# riser.net
KiCad netlist of a schematic drawn in EAGLE
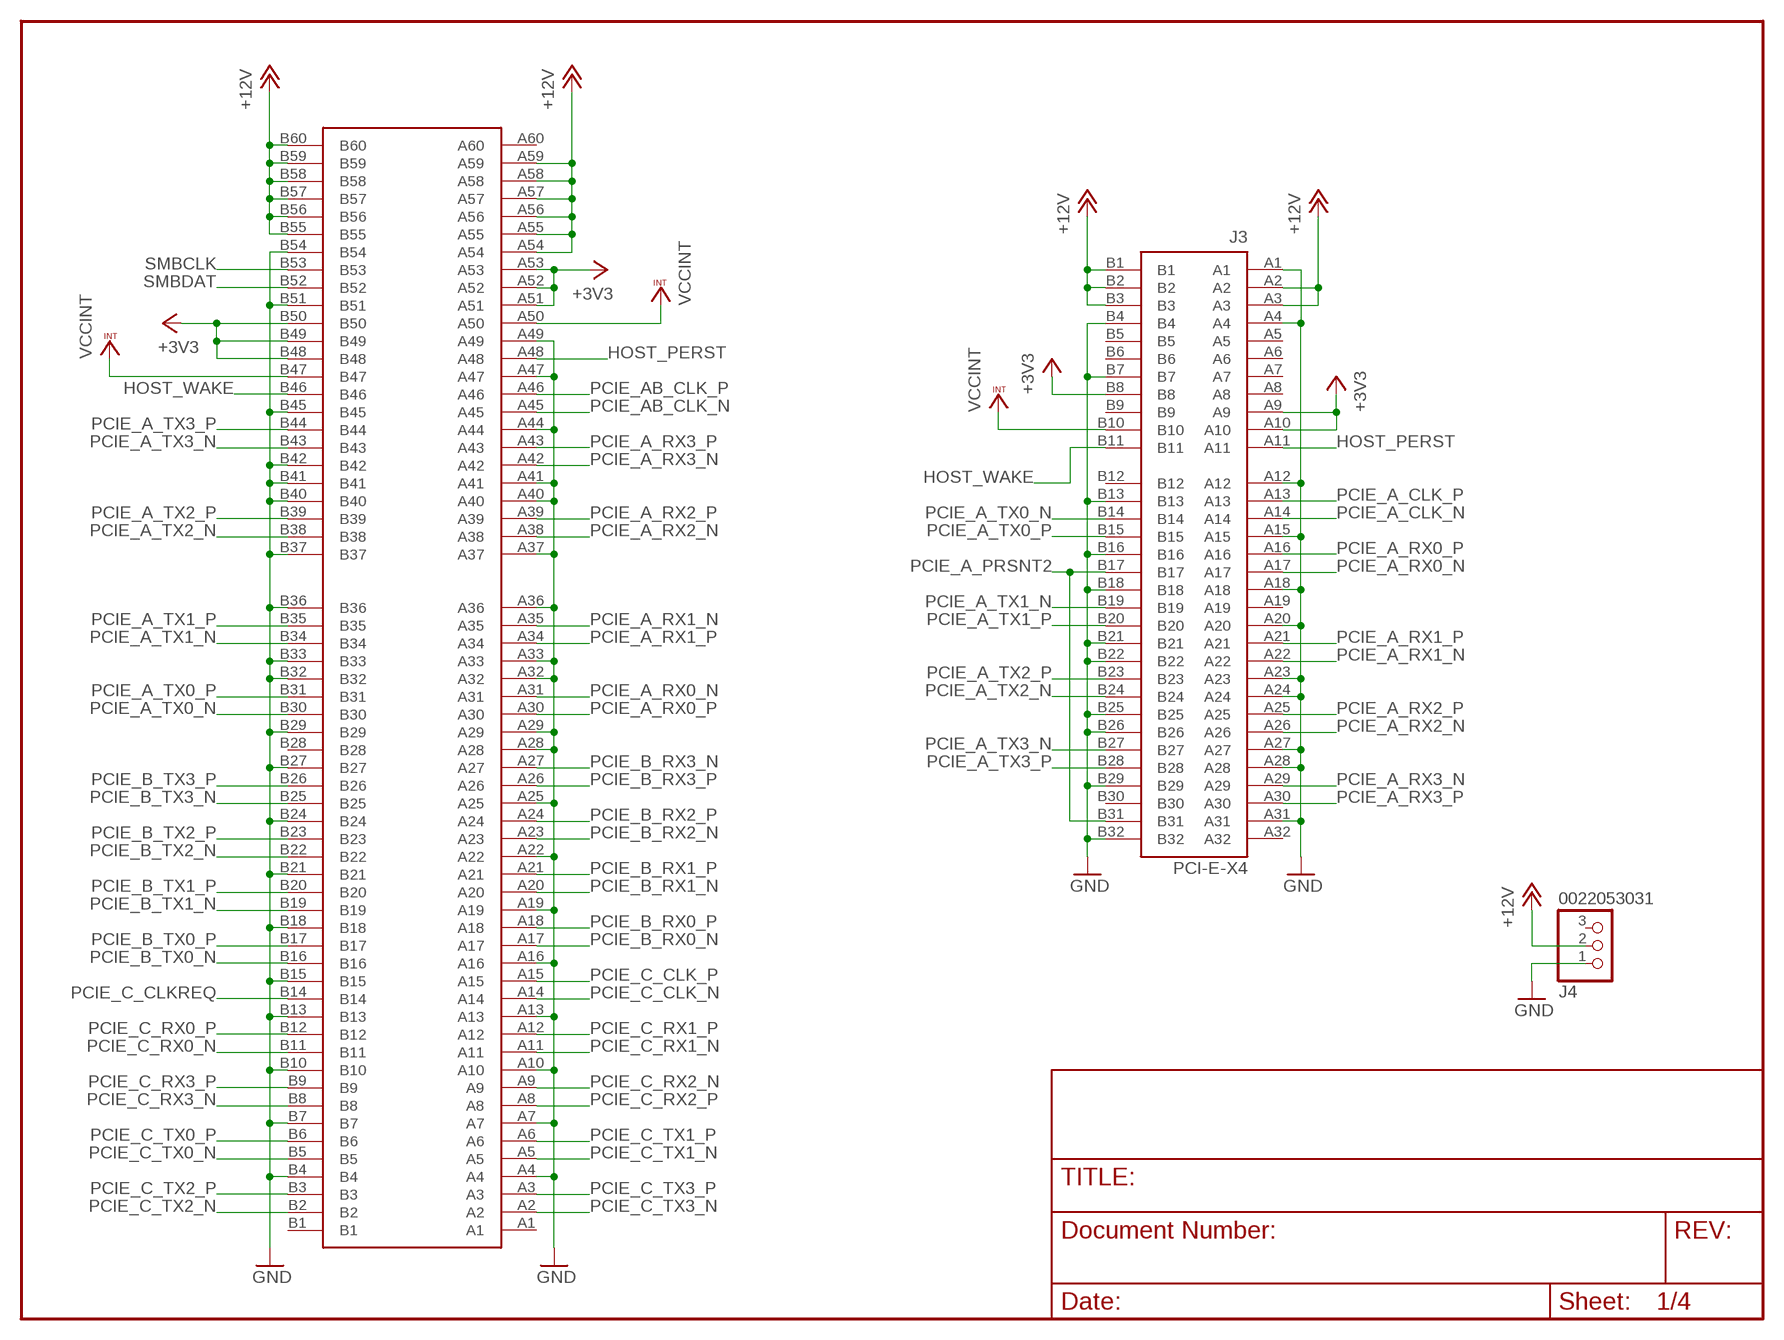
[diagram p0: schematic, sheet 1]
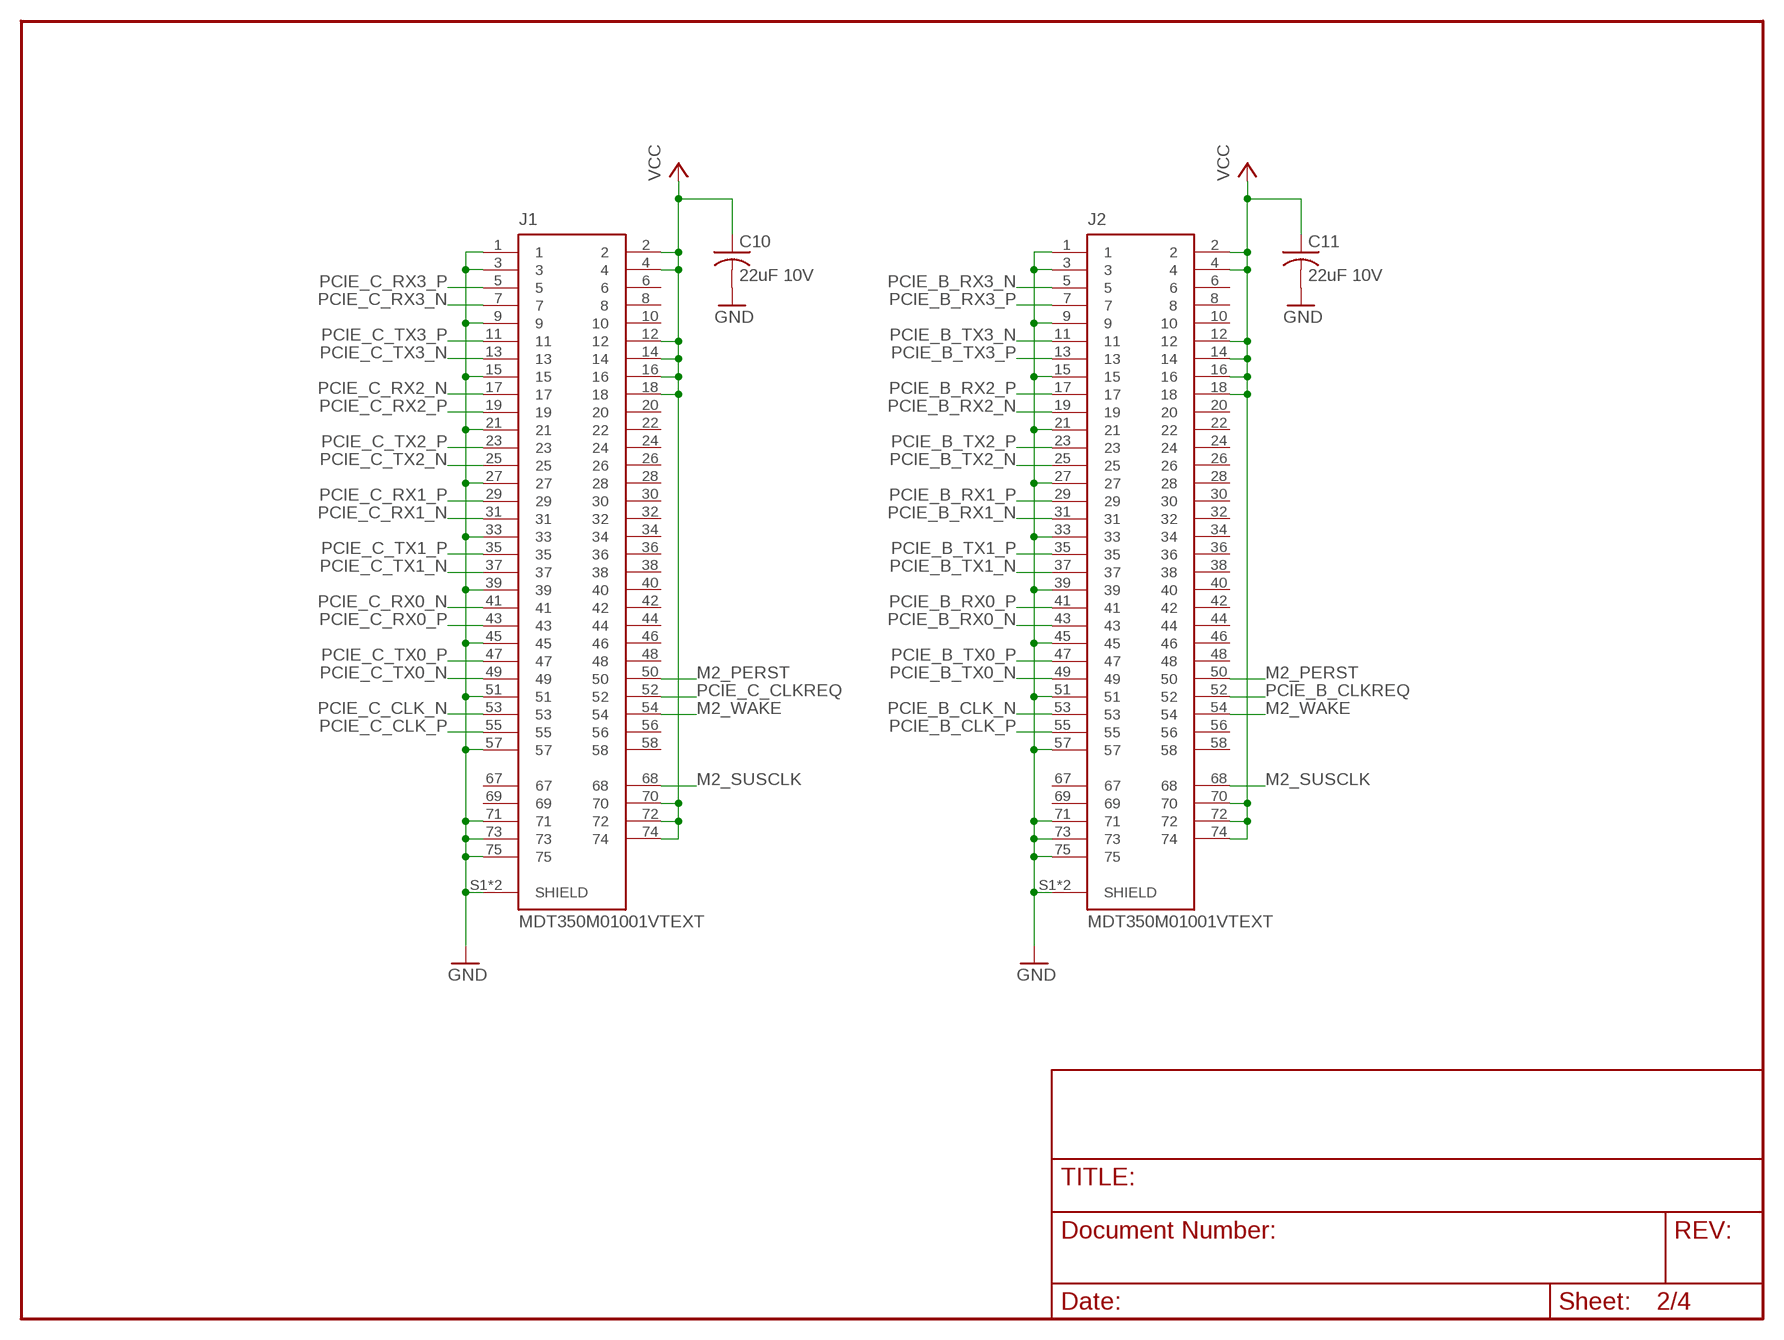
[diagram p1: schematic, sheet 2]
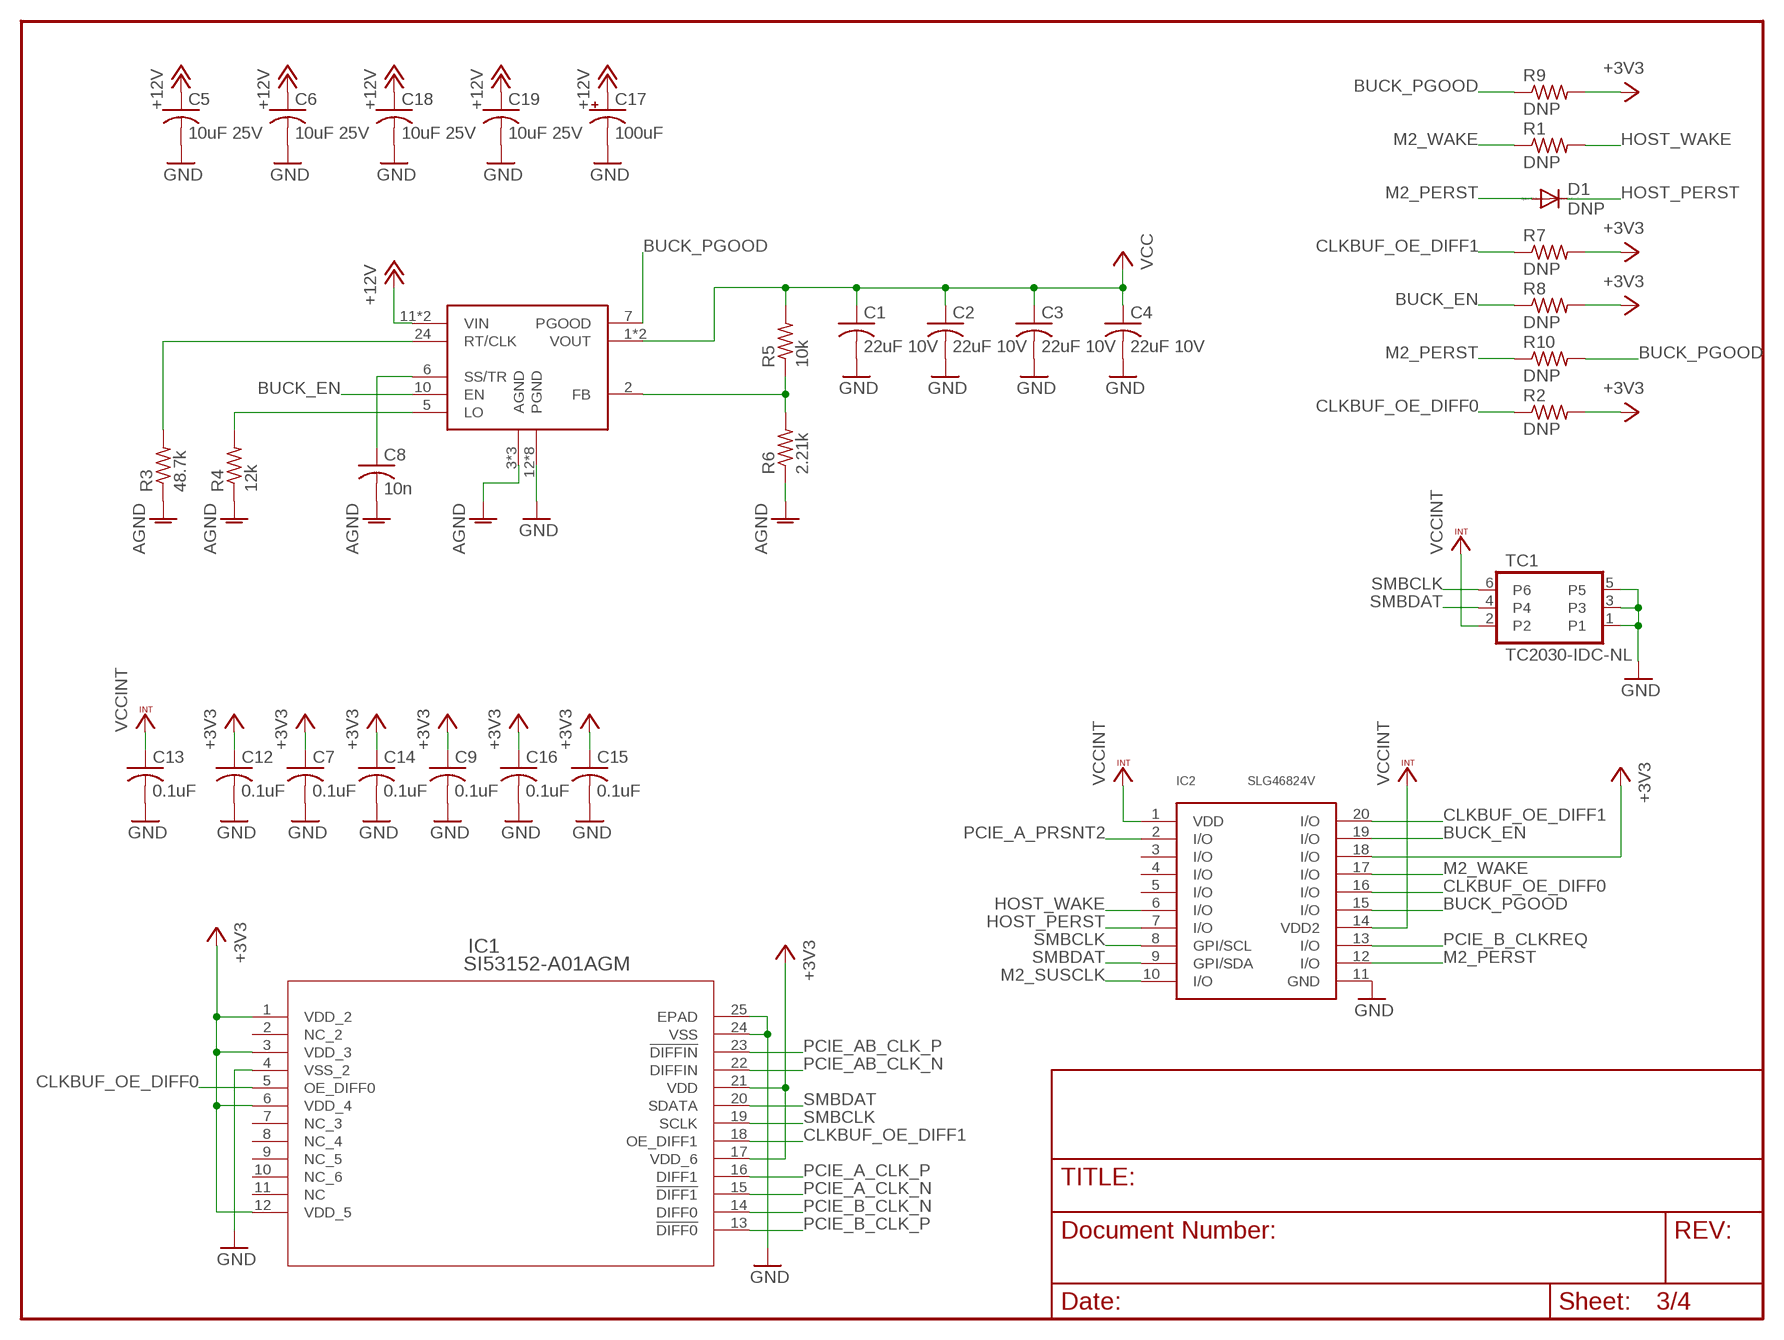
[diagram p2: schematic, sheet 3]
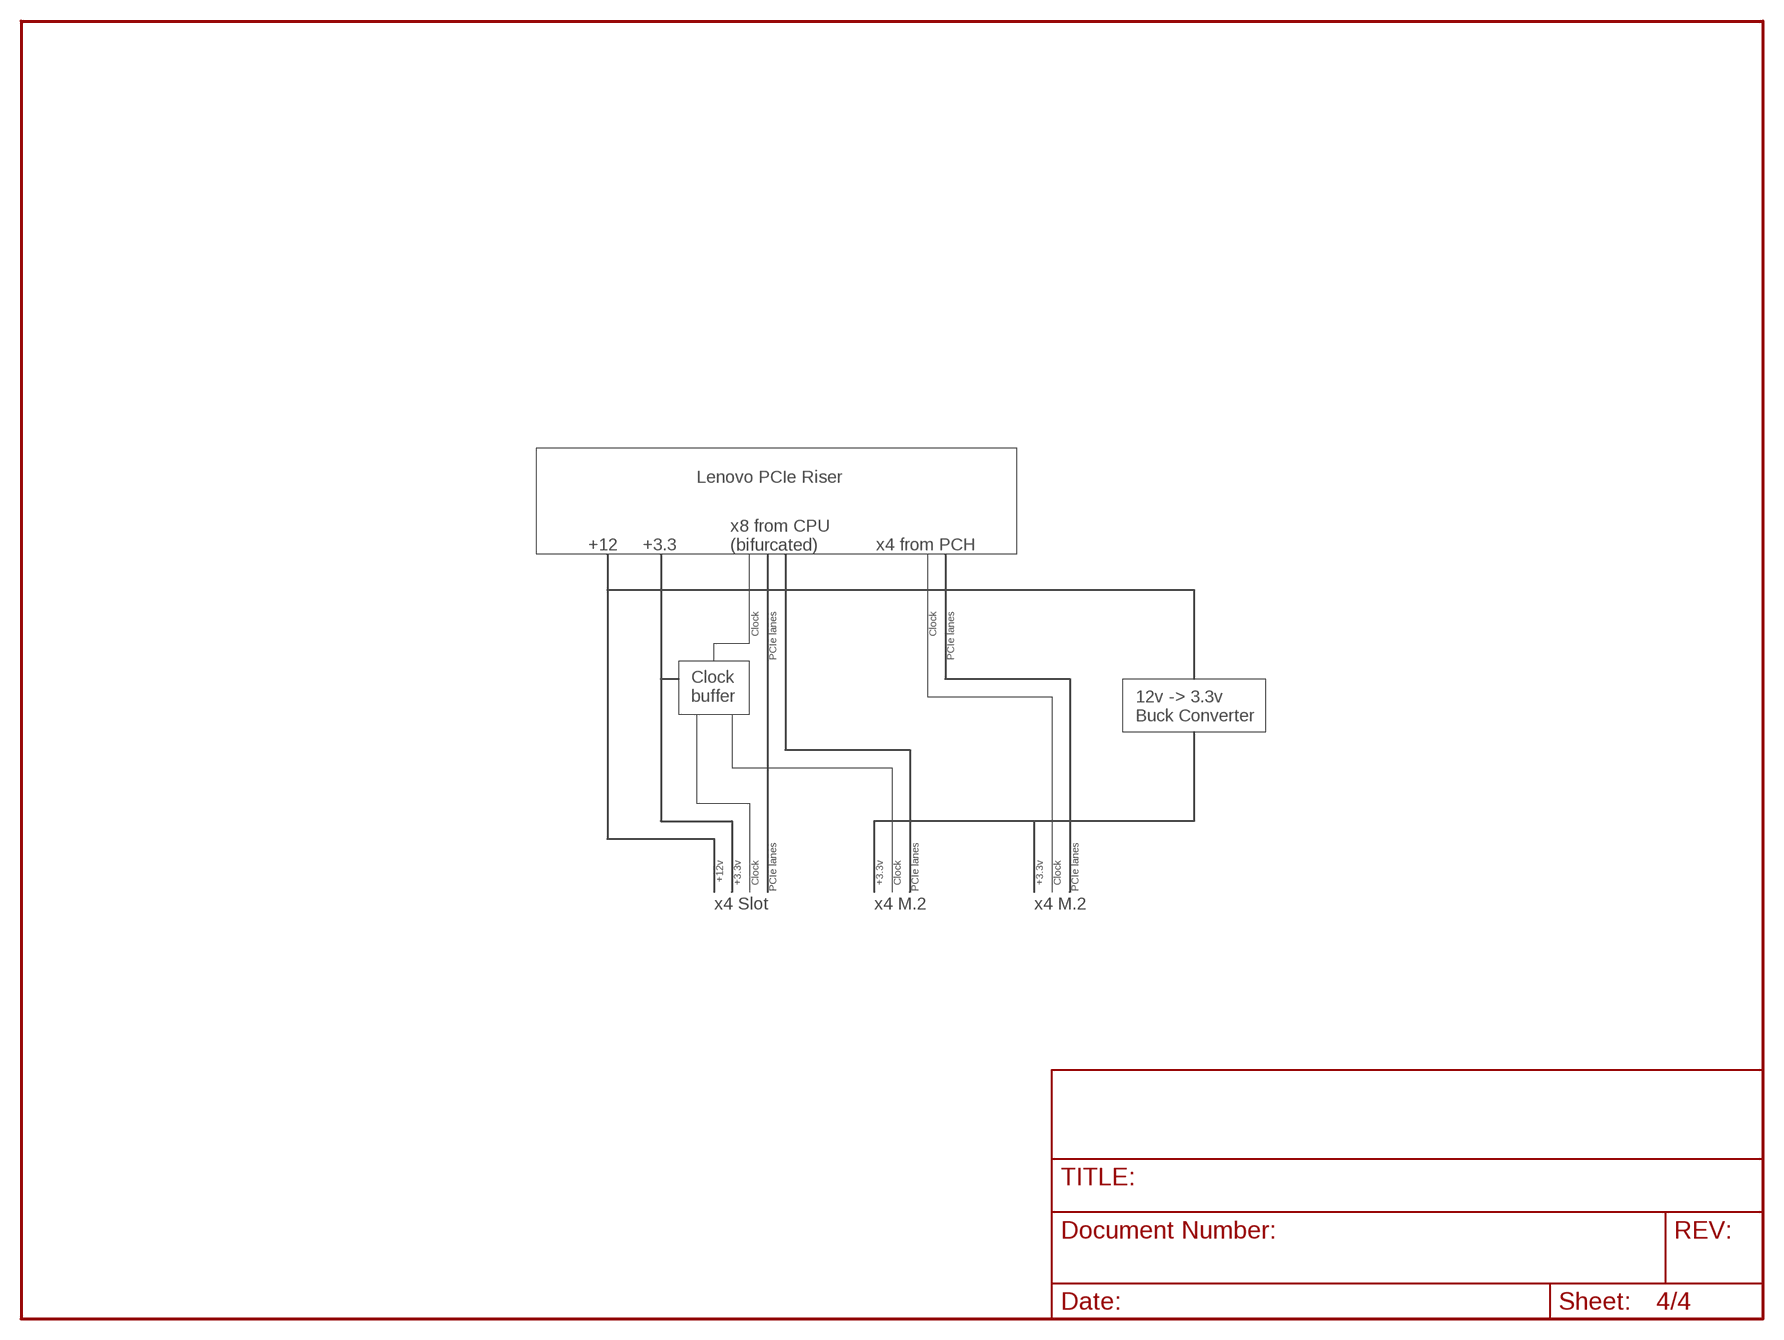
[diagram p3: schematic, sheet 4]

(export (version "E")
  (design (tool "Eeschema 10.0.6"))
  (components
    (comp (ref "C10")
      (value "22uF 10V")
      (footprint "eagle-import:C0805")
      (libsource (lib "eagle-import") (part "resistor_C-USC0805"))
    )
    (comp (ref "C11")
      (value "22uF 10V")
      (footprint "eagle-import:C0805")
      (libsource (lib "eagle-import") (part "resistor_C-USC0805"))
    )
    (comp (ref "J1")
      (value "MDT350M01001VTEXT")
      (footprint "eagle-import:MDT350M01001VT_EXT")
      (libsource (lib "eagle-import") (part "MDT350M01001VTEXT"))
    )
    (comp (ref "J2")
      (value "MDT350M01001VTEXT")
      (footprint "eagle-import:MDT350M01001VT_EXT")
      (libsource (lib "eagle-import") (part "MDT350M01001VTEXT"))
    )
    (comp (ref "C1")
      (value "22uF 10V")
      (footprint "eagle-import:C0805")
      (libsource (lib "eagle-import") (part "resistor_C-USC0805"))
    )
    (comp (ref "C2")
      (value "22uF 10V")
      (footprint "eagle-import:C0805")
      (libsource (lib "eagle-import") (part "resistor_C-USC0805"))
    )
    (comp (ref "C3")
      (value "22uF 10V")
      (footprint "eagle-import:C0805")
      (libsource (lib "eagle-import") (part "resistor_C-USC0805"))
    )
    (comp (ref "C4")
      (value "22uF 10V")
      (footprint "eagle-import:C0805")
      (libsource (lib "eagle-import") (part "resistor_C-USC0805"))
    )
    (comp (ref "C5")
      (value "10uF 25V")
      (footprint "eagle-import:C1210")
      (libsource (lib "eagle-import") (part "resistor_C-USC1210"))
    )
    (comp (ref "C6")
      (value "10uF 25V")
      (footprint "eagle-import:C1210")
      (libsource (lib "eagle-import") (part "resistor_C-USC1210"))
    )
    (comp (ref "C7")
      (value "0.1uF")
      (footprint "eagle-import:C0402")
      (libsource (lib "eagle-import") (part "C-USC0402"))
    )
    (comp (ref "C8")
      (value "10n")
      (footprint "eagle-import:C0402")
      (libsource (lib "eagle-import") (part "C-USC0402"))
    )
    (comp (ref "C9")
      (value "0.1uF")
      (footprint "eagle-import:C0402")
      (libsource (lib "eagle-import") (part "C-USC0402"))
    )
    (comp (ref "C12")
      (value "0.1uF")
      (footprint "eagle-import:C0402")
      (libsource (lib "eagle-import") (part "C-USC0402"))
    )
    (comp (ref "C13")
      (value "0.1uF")
      (footprint "eagle-import:C0402")
      (libsource (lib "eagle-import") (part "C-USC0402"))
    )
    (comp (ref "C14")
      (value "0.1uF")
      (footprint "eagle-import:C0402")
      (libsource (lib "eagle-import") (part "C-USC0402"))
    )
    (comp (ref "C15")
      (value "0.1uF")
      (footprint "eagle-import:C0402")
      (libsource (lib "eagle-import") (part "C-USC0402"))
    )
    (comp (ref "C16")
      (value "0.1uF")
      (footprint "eagle-import:C0402")
      (libsource (lib "eagle-import") (part "C-USC0402"))
    )
    (comp (ref "C17")
      (value "100uF")
      (footprint "eagle-import:E2,5-7")
      (libsource (lib "eagle-import") (part "CPOL-USE2.5-7"))
    )
    (comp (ref "C18")
      (value "10uF 25V")
      (footprint "eagle-import:C0805")
      (libsource (lib "eagle-import") (part "resistor_C-USC0805"))
    )
    (comp (ref "C19")
      (value "10uF 25V")
      (footprint "eagle-import:C0805")
      (libsource (lib "eagle-import") (part "resistor_C-USC0805"))
    )
    (comp (ref "D1")
      (value "DNP")
      (footprint "eagle-import:SOD323-R")
      (libsource (lib "eagle-import") (part "DIODE-SOD323-R"))
    )
    (comp (ref "IC1")
      (value "SI53152-A01AGM")
      (footprint "eagle-import:QFN24_4X4_SIL")
      (fields (field (name "COPYRIGHT") "Copyright (C) 2024 Ultra Librarian. All rights reserved."))
      (libsource (lib "eagle-import") (part "SI53152-A01AGM"))
    )
    (comp (ref "IC2")
      (value "SLG46824V")
      (footprint "eagle-import:STQFN-20L-2.0X2.2-#4")
      (libsource (lib "eagle-import") (part "SLG46824V"))
    )
    (comp (ref "R1")
      (value "DNP")
      (footprint "eagle-import:R0402")
      (libsource (lib "eagle-import") (part "R-US_R0402"))
    )
    (comp (ref "R2")
      (value "DNP")
      (footprint "eagle-import:R0402")
      (libsource (lib "eagle-import") (part "R-US_R0402"))
    )
    (comp (ref "R3")
      (value "48.7k")
      (footprint "eagle-import:R0402")
      (libsource (lib "eagle-import") (part "R-US_R0402"))
    )
    (comp (ref "R4")
      (value "12k")
      (footprint "eagle-import:R0402")
      (libsource (lib "eagle-import") (part "R-US_R0402"))
    )
    (comp (ref "R5")
      (value "10k")
      (footprint "eagle-import:R0402")
      (libsource (lib "eagle-import") (part "R-US_R0402"))
    )
    (comp (ref "R6")
      (value "2.21k")
      (footprint "eagle-import:R0402")
      (libsource (lib "eagle-import") (part "R-US_R0402"))
    )
    (comp (ref "R7")
      (value "DNP")
      (footprint "eagle-import:R0402")
      (libsource (lib "eagle-import") (part "R-US_R0402"))
    )
    (comp (ref "R8")
      (value "DNP")
      (footprint "eagle-import:R0402")
      (libsource (lib "eagle-import") (part "R-US_R0402"))
    )
    (comp (ref "R9")
      (value "DNP")
      (footprint "eagle-import:R0402")
      (libsource (lib "eagle-import") (part "R-US_R0402"))
    )
    (comp (ref "R10")
      (value "DNP")
      (footprint "eagle-import:R0402")
      (libsource (lib "eagle-import") (part "R-US_R0402"))
    )
    (comp (ref "TC1")
      (value "TC2030-IDC-NL")
      (footprint "eagle-import:TC2030-IDC-NL")
      (libsource (lib "eagle-import") (part "TC2030-IDC-NL"))
    )
    (comp (ref "U1")
      (value "PMU8000")
      (footprint "eagle-import:PMU8000")
      (libsource (lib "eagle-import") (part "PMU8000"))
    )
    (comp (ref "J3")
      (value "PCI-E-X4")
      (footprint "eagle-import:PCI-E-X4")
      (libsource (lib "eagle-import") (part "PCI-E-X4"))
    )
    (comp (ref "J4")
      (value "0022053031")
      (footprint "eagle-import:1X03")
      (libsource (lib "eagle-import") (part "PINHD-1X3"))
    )
    (comp (ref "JP1")
      (value "ADDR0262")
      (footprint "eagle-import:ADDR0262-EDGE")
      (libsource (lib "eagle-import") (part "ADDR0262"))
    )
  )
  (nets
    (net (code "1") (name "+3V3") (class "Default")
      (node (ref "C12") (pin "1") (pinfunction "1_1") (pintype "passive"))
      (node (ref "C14") (pin "1") (pinfunction "1_1") (pintype "passive"))
      (node (ref "C15") (pin "1") (pinfunction "1_1") (pintype "passive"))
      (node (ref "C16") (pin "1") (pinfunction "1_1") (pintype "passive"))
      (node (ref "C7") (pin "1") (pinfunction "1_1") (pintype "passive"))
      (node (ref "C9") (pin "1") (pinfunction "1_1") (pintype "passive"))
      (node (ref "IC1") (pin "1") (pinfunction "VDD_2_1") (pintype "power_in"))
      (node (ref "IC1") (pin "12") (pinfunction "VDD_5_12") (pintype "power_in"))
      (node (ref "IC1") (pin "17") (pinfunction "VDD_6_17") (pintype "power_in"))
      (node (ref "IC1") (pin "21") (pinfunction "VDD_21") (pintype "power_in"))
      (node (ref "IC1") (pin "3") (pinfunction "VDD_3_3") (pintype "power_in"))
      (node (ref "IC1") (pin "6") (pinfunction "VDD_4_6") (pintype "power_in"))
      (node (ref "IC2") (pin "18") (pinfunction "I/O_18") (pintype "bidirectional"))
      (node (ref "J3") (pin "A10") (pinfunction "A10_A10") (pintype "passive"))
      (node (ref "J3") (pin "A9") (pinfunction "A9_A9") (pintype "passive"))
      (node (ref "J3") (pin "B8") (pinfunction "B8_B8") (pintype "passive"))
      (node (ref "JP1") (pin "A51") (pinfunction "A51_A51") (pintype "bidirectional"))
      (node (ref "JP1") (pin "A52") (pinfunction "A52_A52") (pintype "bidirectional"))
      (node (ref "JP1") (pin "A53") (pinfunction "A53_A53") (pintype "bidirectional"))
      (node (ref "JP1") (pin "B48") (pinfunction "B48_B48") (pintype "bidirectional"))
      (node (ref "JP1") (pin "B49") (pinfunction "B49_B49") (pintype "bidirectional"))
      (node (ref "JP1") (pin "B50") (pinfunction "B50_B50") (pintype "bidirectional"))
      (node (ref "R2") (pin "2") (pinfunction "2_2") (pintype "passive"))
      (node (ref "R7") (pin "2") (pinfunction "2_2") (pintype "passive"))
      (node (ref "R8") (pin "2") (pinfunction "2_2") (pintype "passive"))
      (node (ref "R9") (pin "2") (pinfunction "2_2") (pintype "passive"))
    )
    (net (code "2") (name "+12V") (class "Default")
      (node (ref "C17") (pin "+") (pinfunction "+_+") (pintype "passive"))
      (node (ref "C18") (pin "1") (pinfunction "1_1") (pintype "passive"))
      (node (ref "C19") (pin "1") (pinfunction "1_1") (pintype "passive"))
      (node (ref "C5") (pin "1") (pinfunction "1_1") (pintype "passive"))
      (node (ref "C6") (pin "1") (pinfunction "1_1") (pintype "passive"))
      (node (ref "J3") (pin "A2") (pinfunction "A2_A2") (pintype "passive"))
      (node (ref "J3") (pin "A3") (pinfunction "A3_A3") (pintype "passive"))
      (node (ref "J3") (pin "B1") (pinfunction "B1_B1") (pintype "passive"))
      (node (ref "J3") (pin "B2") (pinfunction "B2_B2") (pintype "passive"))
      (node (ref "J3") (pin "B3") (pinfunction "B3_B3") (pintype "passive"))
      (node (ref "J4") (pin "2") (pinfunction "2_2") (pintype "passive"))
      (node (ref "JP1") (pin "A54") (pinfunction "A54_A54") (pintype "bidirectional"))
      (node (ref "JP1") (pin "A55") (pinfunction "A55_A55") (pintype "bidirectional"))
      (node (ref "JP1") (pin "A56") (pinfunction "A56_A56") (pintype "bidirectional"))
      (node (ref "JP1") (pin "A57") (pinfunction "A57_A57") (pintype "bidirectional"))
      (node (ref "JP1") (pin "A58") (pinfunction "A58_A58") (pintype "bidirectional"))
      (node (ref "JP1") (pin "A59") (pinfunction "A59_A59") (pintype "bidirectional"))
      (node (ref "JP1") (pin "B55") (pinfunction "B55_B55") (pintype "bidirectional"))
      (node (ref "JP1") (pin "B56") (pinfunction "B56_B56") (pintype "bidirectional"))
      (node (ref "JP1") (pin "B57") (pinfunction "B57_B57") (pintype "bidirectional"))
      (node (ref "JP1") (pin "B58") (pinfunction "B58_B58") (pintype "bidirectional"))
      (node (ref "JP1") (pin "B59") (pinfunction "B59_B59") (pintype "bidirectional"))
      (node (ref "JP1") (pin "B60") (pinfunction "B60_B60") (pintype "bidirectional"))
      (node (ref "U1") (pin "11") (pinfunction "VIN_11") (pintype "bidirectional"))
      (node (ref "U1") (pin "22") (pinfunction "VIN_22") (pintype "bidirectional"))
    )
    (net (code "3") (name "AGND") (class "Default")
      (node (ref "C8") (pin "2") (pinfunction "2_2") (pintype "passive"))
      (node (ref "R3") (pin "1") (pinfunction "1_1") (pintype "passive"))
      (node (ref "R4") (pin "1") (pinfunction "1_1") (pintype "passive"))
      (node (ref "R6") (pin "1") (pinfunction "1_1") (pintype "passive"))
      (node (ref "U1") (pin "23") (pinfunction "AGND_23") (pintype "bidirectional"))
      (node (ref "U1") (pin "3") (pinfunction "AGND_3") (pintype "bidirectional"))
      (node (ref "U1") (pin "9") (pinfunction "AGND_9") (pintype "bidirectional"))
    )
    (net (code "4") (name "BUCK_EN") (class "Default")
      (node (ref "IC2") (pin "19") (pinfunction "I/O_19") (pintype "bidirectional"))
      (node (ref "R8") (pin "1") (pinfunction "1_1") (pintype "passive"))
      (node (ref "U1") (pin "10") (pinfunction "EN_10") (pintype "bidirectional"))
    )
    (net (code "5") (name "BUCK_PGOOD") (class "Default")
      (node (ref "IC2") (pin "15") (pinfunction "I/O_15") (pintype "bidirectional"))
      (node (ref "R10") (pin "2") (pinfunction "2_2") (pintype "passive"))
      (node (ref "R9") (pin "1") (pinfunction "1_1") (pintype "passive"))
      (node (ref "U1") (pin "7") (pinfunction "PGOOD_7") (pintype "bidirectional"))
    )
    (net (code "6") (name "CLKBUF_OE_DIFF0") (class "Default")
      (node (ref "IC1") (pin "5") (pinfunction "OE_DIFF0_5") (pintype "input"))
      (node (ref "IC2") (pin "16") (pinfunction "I/O_16") (pintype "bidirectional"))
      (node (ref "R2") (pin "1") (pinfunction "1_1") (pintype "passive"))
    )
    (net (code "7") (name "CLKBUF_OE_DIFF1") (class "Default")
      (node (ref "IC1") (pin "18") (pinfunction "OE_DIFF1_18") (pintype "input"))
      (node (ref "IC2") (pin "20") (pinfunction "I/O_20") (pintype "bidirectional"))
      (node (ref "R7") (pin "1") (pinfunction "1_1") (pintype "passive"))
    )
    (net (code "8") (name "GND") (class "Default")
      (node (ref "C1") (pin "2") (pinfunction "2_2") (pintype "passive"))
      (node (ref "C10") (pin "2") (pinfunction "2_2") (pintype "passive"))
      (node (ref "C11") (pin "2") (pinfunction "2_2") (pintype "passive"))
      (node (ref "C12") (pin "2") (pinfunction "2_2") (pintype "passive"))
      (node (ref "C13") (pin "2") (pinfunction "2_2") (pintype "passive"))
      (node (ref "C14") (pin "2") (pinfunction "2_2") (pintype "passive"))
      (node (ref "C15") (pin "2") (pinfunction "2_2") (pintype "passive"))
      (node (ref "C16") (pin "2") (pinfunction "2_2") (pintype "passive"))
      (node (ref "C17") (pin "-") (pinfunction "-_-") (pintype "passive"))
      (node (ref "C18") (pin "2") (pinfunction "2_2") (pintype "passive"))
      (node (ref "C19") (pin "2") (pinfunction "2_2") (pintype "passive"))
      (node (ref "C2") (pin "2") (pinfunction "2_2") (pintype "passive"))
      (node (ref "C3") (pin "2") (pinfunction "2_2") (pintype "passive"))
      (node (ref "C4") (pin "2") (pinfunction "2_2") (pintype "passive"))
      (node (ref "C5") (pin "2") (pinfunction "2_2") (pintype "passive"))
      (node (ref "C6") (pin "2") (pinfunction "2_2") (pintype "passive"))
      (node (ref "C7") (pin "2") (pinfunction "2_2") (pintype "passive"))
      (node (ref "C9") (pin "2") (pinfunction "2_2") (pintype "passive"))
      (node (ref "IC1") (pin "24") (pinfunction "VSS_24") (pintype "power_in"))
      (node (ref "IC1") (pin "25") (pinfunction "EPAD_25") (pintype "passive"))
      (node (ref "IC1") (pin "4") (pinfunction "VSS_2_4") (pintype "power_in"))
      (node (ref "IC2") (pin "11") (pinfunction "GND_11") (pintype "power_in"))
      (node (ref "J1") (pin "1") (pinfunction "1_1") (pintype "passive"))
      (node (ref "J1") (pin "15") (pinfunction "15_15") (pintype "passive"))
      (node (ref "J1") (pin "21") (pinfunction "21_21") (pintype "passive"))
      (node (ref "J1") (pin "27") (pinfunction "27_27") (pintype "passive"))
      (node (ref "J1") (pin "3") (pinfunction "3_3") (pintype "passive"))
      (node (ref "J1") (pin "33") (pinfunction "33_33") (pintype "passive"))
      (node (ref "J1") (pin "39") (pinfunction "39_39") (pintype "passive"))
      (node (ref "J1") (pin "45") (pinfunction "45_45") (pintype "passive"))
      (node (ref "J1") (pin "51") (pinfunction "51_51") (pintype "passive"))
      (node (ref "J1") (pin "57") (pinfunction "57_57") (pintype "passive"))
      (node (ref "J1") (pin "71") (pinfunction "71_71") (pintype "passive"))
      (node (ref "J1") (pin "73") (pinfunction "73_73") (pintype "passive"))
      (node (ref "J1") (pin "75") (pinfunction "75_75") (pintype "passive"))
      (node (ref "J1") (pin "9") (pinfunction "9_9") (pintype "passive"))
      (node (ref "J1") (pin "S1") (pinfunction "SHIELD_S1") (pintype "passive"))
      (node (ref "J1") (pin "S2") (pinfunction "SHIELD_S2") (pintype "passive"))
      (node (ref "J2") (pin "1") (pinfunction "1_1") (pintype "passive"))
      (node (ref "J2") (pin "15") (pinfunction "15_15") (pintype "passive"))
      (node (ref "J2") (pin "21") (pinfunction "21_21") (pintype "passive"))
      (node (ref "J2") (pin "27") (pinfunction "27_27") (pintype "passive"))
      (node (ref "J2") (pin "3") (pinfunction "3_3") (pintype "passive"))
      (node (ref "J2") (pin "33") (pinfunction "33_33") (pintype "passive"))
      (node (ref "J2") (pin "39") (pinfunction "39_39") (pintype "passive"))
      (node (ref "J2") (pin "45") (pinfunction "45_45") (pintype "passive"))
      (node (ref "J2") (pin "51") (pinfunction "51_51") (pintype "passive"))
      (node (ref "J2") (pin "57") (pinfunction "57_57") (pintype "passive"))
      (node (ref "J2") (pin "71") (pinfunction "71_71") (pintype "passive"))
      (node (ref "J2") (pin "73") (pinfunction "73_73") (pintype "passive"))
      (node (ref "J2") (pin "75") (pinfunction "75_75") (pintype "passive"))
      (node (ref "J2") (pin "9") (pinfunction "9_9") (pintype "passive"))
      (node (ref "J2") (pin "S1") (pinfunction "SHIELD_S1") (pintype "passive"))
      (node (ref "J2") (pin "S2") (pinfunction "SHIELD_S2") (pintype "passive"))
      (node (ref "J3") (pin "A1") (pinfunction "A1_A1") (pintype "passive"))
      (node (ref "J3") (pin "A12") (pinfunction "A12_A12") (pintype "passive"))
      (node (ref "J3") (pin "A15") (pinfunction "A15_A15") (pintype "passive"))
      (node (ref "J3") (pin "A18") (pinfunction "A18_A18") (pintype "passive"))
      (node (ref "J3") (pin "A20") (pinfunction "A20_A20") (pintype "passive"))
      (node (ref "J3") (pin "A23") (pinfunction "A23_A23") (pintype "passive"))
      (node (ref "J3") (pin "A24") (pinfunction "A24_A24") (pintype "passive"))
      (node (ref "J3") (pin "A27") (pinfunction "A27_A27") (pintype "passive"))
      (node (ref "J3") (pin "A28") (pinfunction "A28_A28") (pintype "passive"))
      (node (ref "J3") (pin "A31") (pinfunction "A31_A31") (pintype "passive"))
      (node (ref "J3") (pin "A4") (pinfunction "A4_A4") (pintype "passive"))
      (node (ref "J3") (pin "B13") (pinfunction "B13_B13") (pintype "passive"))
      (node (ref "J3") (pin "B16") (pinfunction "B16_B16") (pintype "passive"))
      (node (ref "J3") (pin "B18") (pinfunction "B18_B18") (pintype "passive"))
      (node (ref "J3") (pin "B21") (pinfunction "B21_B21") (pintype "passive"))
      (node (ref "J3") (pin "B22") (pinfunction "B22_B22") (pintype "passive"))
      (node (ref "J3") (pin "B25") (pinfunction "B25_B25") (pintype "passive"))
      (node (ref "J3") (pin "B26") (pinfunction "B26_B26") (pintype "passive"))
      (node (ref "J3") (pin "B29") (pinfunction "B29_B29") (pintype "passive"))
      (node (ref "J3") (pin "B32") (pinfunction "B32_B32") (pintype "passive"))
      (node (ref "J3") (pin "B4") (pinfunction "B4_B4") (pintype "passive"))
      (node (ref "J3") (pin "B7") (pinfunction "B7_B7") (pintype "passive"))
      (node (ref "J4") (pin "1") (pinfunction "1_1") (pintype "passive"))
      (node (ref "JP1") (pin "A10") (pinfunction "A10_A10") (pintype "bidirectional"))
      (node (ref "JP1") (pin "A13") (pinfunction "A13_A13") (pintype "bidirectional"))
      (node (ref "JP1") (pin "A16") (pinfunction "A16_A16") (pintype "bidirectional"))
      (node (ref "JP1") (pin "A19") (pinfunction "A19_A19") (pintype "bidirectional"))
      (node (ref "JP1") (pin "A22") (pinfunction "A22_A22") (pintype "bidirectional"))
      (node (ref "JP1") (pin "A25") (pinfunction "A25_A25") (pintype "bidirectional"))
      (node (ref "JP1") (pin "A28") (pinfunction "A28_A28") (pintype "bidirectional"))
      (node (ref "JP1") (pin "A29") (pinfunction "A29_A29") (pintype "bidirectional"))
      (node (ref "JP1") (pin "A32") (pinfunction "A32_A32") (pintype "bidirectional"))
      (node (ref "JP1") (pin "A33") (pinfunction "A33_A33") (pintype "bidirectional"))
      (node (ref "JP1") (pin "A36") (pinfunction "A36_A36") (pintype "bidirectional"))
      (node (ref "JP1") (pin "A37") (pinfunction "A37_A37") (pintype "bidirectional"))
      (node (ref "JP1") (pin "A4") (pinfunction "A4_A4") (pintype "bidirectional"))
      (node (ref "JP1") (pin "A40") (pinfunction "A40_A40") (pintype "bidirectional"))
      (node (ref "JP1") (pin "A41") (pinfunction "A41_A41") (pintype "bidirectional"))
      (node (ref "JP1") (pin "A44") (pinfunction "A44_A44") (pintype "bidirectional"))
      (node (ref "JP1") (pin "A47") (pinfunction "A47_A47") (pintype "bidirectional"))
      (node (ref "JP1") (pin "A49") (pinfunction "A49_A49") (pintype "bidirectional"))
      (node (ref "JP1") (pin "A7") (pinfunction "A7_A7") (pintype "bidirectional"))
      (node (ref "JP1") (pin "B10") (pinfunction "B10_B10") (pintype "bidirectional"))
      (node (ref "JP1") (pin "B13") (pinfunction "B13_B13") (pintype "bidirectional"))
      (node (ref "JP1") (pin "B15") (pinfunction "B15_B15") (pintype "bidirectional"))
      (node (ref "JP1") (pin "B18") (pinfunction "B18_B18") (pintype "bidirectional"))
      (node (ref "JP1") (pin "B21") (pinfunction "B21_B21") (pintype "bidirectional"))
      (node (ref "JP1") (pin "B24") (pinfunction "B24_B24") (pintype "bidirectional"))
      (node (ref "JP1") (pin "B27") (pinfunction "B27_B27") (pintype "bidirectional"))
      (node (ref "JP1") (pin "B29") (pinfunction "B29_B29") (pintype "bidirectional"))
      (node (ref "JP1") (pin "B32") (pinfunction "B32_B32") (pintype "bidirectional"))
      (node (ref "JP1") (pin "B33") (pinfunction "B33_B33") (pintype "bidirectional"))
      (node (ref "JP1") (pin "B36") (pinfunction "B36_B36") (pintype "bidirectional"))
      (node (ref "JP1") (pin "B37") (pinfunction "B37_B37") (pintype "bidirectional"))
      (node (ref "JP1") (pin "B4") (pinfunction "B4_B4") (pintype "bidirectional"))
      (node (ref "JP1") (pin "B40") (pinfunction "B40_B40") (pintype "bidirectional"))
      (node (ref "JP1") (pin "B41") (pinfunction "B41_B41") (pintype "bidirectional"))
      (node (ref "JP1") (pin "B42") (pinfunction "B42_B42") (pintype "bidirectional"))
      (node (ref "JP1") (pin "B45") (pinfunction "B45_B45") (pintype "bidirectional"))
      (node (ref "JP1") (pin "B51") (pinfunction "B51_B51") (pintype "bidirectional"))
      (node (ref "JP1") (pin "B54") (pinfunction "B54_B54") (pintype "bidirectional"))
      (node (ref "JP1") (pin "B7") (pinfunction "B7_B7") (pintype "bidirectional"))
      (node (ref "TC1") (pin "1") (pinfunction "P1_1") (pintype "passive"))
      (node (ref "TC1") (pin "3") (pinfunction "P3_3") (pintype "passive"))
      (node (ref "TC1") (pin "5") (pinfunction "P5_5") (pintype "passive"))
      (node (ref "U1") (pin "12") (pinfunction "PGND_12") (pintype "bidirectional"))
      (node (ref "U1") (pin "13") (pinfunction "PGND_13") (pintype "bidirectional"))
      (node (ref "U1") (pin "14") (pinfunction "PGND_14") (pintype "bidirectional"))
      (node (ref "U1") (pin "15") (pinfunction "PGND_15") (pintype "bidirectional"))
      (node (ref "U1") (pin "18") (pinfunction "PGND_18") (pintype "bidirectional"))
      (node (ref "U1") (pin "19") (pinfunction "PGND_19") (pintype "bidirectional"))
      (node (ref "U1") (pin "20") (pinfunction "PGND_20") (pintype "bidirectional"))
      (node (ref "U1") (pin "21") (pinfunction "PGND_21") (pintype "bidirectional"))
    )
    (net (code "9") (name "HOST_PERST") (class "Default")
      (node (ref "D1") (pin "C") (pinfunction "C_C") (pintype "passive"))
      (node (ref "IC2") (pin "7") (pinfunction "I/O_7") (pintype "bidirectional"))
      (node (ref "J3") (pin "A11") (pinfunction "A11_A11") (pintype "passive"))
      (node (ref "JP1") (pin "A48") (pinfunction "A48_A48") (pintype "bidirectional"))
    )
    (net (code "10") (name "HOST_WAKE") (class "Default")
      (node (ref "IC2") (pin "6") (pinfunction "I/O_6") (pintype "bidirectional"))
      (node (ref "J3") (pin "B11") (pinfunction "B11_B11") (pintype "passive"))
      (node (ref "JP1") (pin "B46") (pinfunction "B46_B46") (pintype "bidirectional"))
      (node (ref "R1") (pin "2") (pinfunction "2_2") (pintype "passive"))
    )
    (net (code "11") (name "M2_PERST") (class "Default")
      (node (ref "D1") (pin "A") (pinfunction "A_A") (pintype "passive"))
      (node (ref "IC2") (pin "12") (pinfunction "I/O_12") (pintype "bidirectional"))
      (node (ref "J1") (pin "50") (pinfunction "50_50") (pintype "passive"))
      (node (ref "J2") (pin "50") (pinfunction "50_50") (pintype "passive"))
      (node (ref "R10") (pin "1") (pinfunction "1_1") (pintype "passive"))
    )
    (net (code "12") (name "M2_SUSCLK") (class "Default")
      (node (ref "IC2") (pin "10") (pinfunction "I/O_10") (pintype "bidirectional"))
      (node (ref "J1") (pin "68") (pinfunction "68_68") (pintype "passive"))
      (node (ref "J2") (pin "68") (pinfunction "68_68") (pintype "passive"))
    )
    (net (code "13") (name "M2_WAKE") (class "Default")
      (node (ref "IC2") (pin "17") (pinfunction "I/O_17") (pintype "bidirectional"))
      (node (ref "J1") (pin "54") (pinfunction "54_54") (pintype "passive"))
      (node (ref "J2") (pin "54") (pinfunction "54_54") (pintype "passive"))
      (node (ref "R1") (pin "1") (pinfunction "1_1") (pintype "passive"))
    )
    (net (code "14") (name "Net-(U1-FB)") (class "Default")
      (node (ref "R5") (pin "1") (pinfunction "1_1") (pintype "passive"))
      (node (ref "R6") (pin "2") (pinfunction "2_2") (pintype "passive"))
      (node (ref "U1") (pin "2") (pinfunction "FB_2") (pintype "bidirectional"))
    )
    (net (code "15") (name "Net-(U1-LO)") (class "Default")
      (node (ref "R4") (pin "2") (pinfunction "2_2") (pintype "passive"))
      (node (ref "U1") (pin "5") (pinfunction "LO_5") (pintype "bidirectional"))
    )
    (net (code "16") (name "Net-(U1-RT{slash}CLK)") (class "Default")
      (node (ref "R3") (pin "2") (pinfunction "2_2") (pintype "passive"))
      (node (ref "U1") (pin "24") (pinfunction "RT/CLK_24") (pintype "bidirectional"))
    )
    (net (code "17") (name "Net-(U1-SS{slash}TR)") (class "Default")
      (node (ref "C8") (pin "1") (pinfunction "1_1") (pintype "passive"))
      (node (ref "U1") (pin "6") (pinfunction "SS/TR_6") (pintype "bidirectional"))
    )
    (net (code "18") (name "PCIE_AB_CLK_N") (class "Default")
      (node (ref "IC1") (pin "22") (pinfunction "DIFFIN_22") (pintype "input"))
      (node (ref "JP1") (pin "A45") (pinfunction "A45_A45") (pintype "bidirectional"))
    )
    (net (code "19") (name "PCIE_AB_CLK_P") (class "Default")
      (node (ref "IC1") (pin "23") (pinfunction "~{DIFFIN}_23") (pintype "input"))
      (node (ref "JP1") (pin "A46") (pinfunction "A46_A46") (pintype "bidirectional"))
    )
    (net (code "20") (name "PCIE_A_CLK_N") (class "Default")
      (node (ref "IC1") (pin "15") (pinfunction "~{DIFF1}_15") (pintype "output"))
      (node (ref "J3") (pin "A14") (pinfunction "A14_A14") (pintype "passive"))
    )
    (net (code "21") (name "PCIE_A_CLK_P") (class "Default")
      (node (ref "IC1") (pin "16") (pinfunction "DIFF1_16") (pintype "output"))
      (node (ref "J3") (pin "A13") (pinfunction "A13_A13") (pintype "passive"))
    )
    (net (code "22") (name "PCIE_A_PRSNT2") (class "Default")
      (node (ref "IC2") (pin "2") (pinfunction "I/O_2") (pintype "input"))
      (node (ref "J3") (pin "B17") (pinfunction "B17_B17") (pintype "passive"))
      (node (ref "J3") (pin "B31") (pinfunction "B31_B31") (pintype "passive"))
    )
    (net (code "23") (name "PCIE_A_RX0_N") (class "Default")
      (node (ref "J3") (pin "A17") (pinfunction "A17_A17") (pintype "passive"))
      (node (ref "JP1") (pin "A31") (pinfunction "A31_A31") (pintype "bidirectional"))
    )
    (net (code "24") (name "PCIE_A_RX0_P") (class "Default")
      (node (ref "J3") (pin "A16") (pinfunction "A16_A16") (pintype "passive"))
      (node (ref "JP1") (pin "A30") (pinfunction "A30_A30") (pintype "bidirectional"))
    )
    (net (code "25") (name "PCIE_A_RX1_N") (class "Default")
      (node (ref "J3") (pin "A22") (pinfunction "A22_A22") (pintype "passive"))
      (node (ref "JP1") (pin "A35") (pinfunction "A35_A35") (pintype "bidirectional"))
    )
    (net (code "26") (name "PCIE_A_RX1_P") (class "Default")
      (node (ref "J3") (pin "A21") (pinfunction "A21_A21") (pintype "passive"))
      (node (ref "JP1") (pin "A34") (pinfunction "A34_A34") (pintype "bidirectional"))
    )
    (net (code "27") (name "PCIE_A_RX2_N") (class "Default")
      (node (ref "J3") (pin "A26") (pinfunction "A26_A26") (pintype "passive"))
      (node (ref "JP1") (pin "A38") (pinfunction "A38_A38") (pintype "bidirectional"))
    )
    (net (code "28") (name "PCIE_A_RX2_P") (class "Default")
      (node (ref "J3") (pin "A25") (pinfunction "A25_A25") (pintype "passive"))
      (node (ref "JP1") (pin "A39") (pinfunction "A39_A39") (pintype "bidirectional"))
    )
    (net (code "29") (name "PCIE_A_RX3_N") (class "Default")
      (node (ref "J3") (pin "A29") (pinfunction "A29_A29") (pintype "passive"))
      (node (ref "JP1") (pin "A42") (pinfunction "A42_A42") (pintype "bidirectional"))
    )
    (net (code "30") (name "PCIE_A_RX3_P") (class "Default")
      (node (ref "J3") (pin "A30") (pinfunction "A30_A30") (pintype "passive"))
      (node (ref "JP1") (pin "A43") (pinfunction "A43_A43") (pintype "bidirectional"))
    )
    (net (code "31") (name "PCIE_A_TX0_N") (class "Default")
      (node (ref "J3") (pin "B14") (pinfunction "B14_B14") (pintype "passive"))
      (node (ref "JP1") (pin "B30") (pinfunction "B30_B30") (pintype "bidirectional"))
    )
    (net (code "32") (name "PCIE_A_TX0_P") (class "Default")
      (node (ref "J3") (pin "B15") (pinfunction "B15_B15") (pintype "passive"))
      (node (ref "JP1") (pin "B31") (pinfunction "B31_B31") (pintype "bidirectional"))
    )
    (net (code "33") (name "PCIE_A_TX1_N") (class "Default")
      (node (ref "J3") (pin "B19") (pinfunction "B19_B19") (pintype "passive"))
      (node (ref "JP1") (pin "B34") (pinfunction "B34_B34") (pintype "bidirectional"))
    )
    (net (code "34") (name "PCIE_A_TX1_P") (class "Default")
      (node (ref "J3") (pin "B20") (pinfunction "B20_B20") (pintype "passive"))
      (node (ref "JP1") (pin "B35") (pinfunction "B35_B35") (pintype "bidirectional"))
    )
    (net (code "35") (name "PCIE_A_TX2_N") (class "Default")
      (node (ref "J3") (pin "B24") (pinfunction "B24_B24") (pintype "passive"))
      (node (ref "JP1") (pin "B38") (pinfunction "B38_B38") (pintype "bidirectional"))
    )
    (net (code "36") (name "PCIE_A_TX2_P") (class "Default")
      (node (ref "J3") (pin "B23") (pinfunction "B23_B23") (pintype "passive"))
      (node (ref "JP1") (pin "B39") (pinfunction "B39_B39") (pintype "bidirectional"))
    )
    (net (code "37") (name "PCIE_A_TX3_N") (class "Default")
      (node (ref "J3") (pin "B27") (pinfunction "B27_B27") (pintype "passive"))
      (node (ref "JP1") (pin "B43") (pinfunction "B43_B43") (pintype "bidirectional"))
    )
    (net (code "38") (name "PCIE_A_TX3_P") (class "Default")
      (node (ref "J3") (pin "B28") (pinfunction "B28_B28") (pintype "passive"))
      (node (ref "JP1") (pin "B44") (pinfunction "B44_B44") (pintype "bidirectional"))
    )
    (net (code "39") (name "PCIE_B_CLKREQ") (class "Default")
      (node (ref "IC2") (pin "13") (pinfunction "I/O_13") (pintype "bidirectional"))
      (node (ref "J2") (pin "52") (pinfunction "52_52") (pintype "passive"))
    )
    (net (code "40") (name "PCIE_B_CLK_N") (class "Default")
      (node (ref "IC1") (pin "14") (pinfunction "DIFF0_14") (pintype "output"))
      (node (ref "J2") (pin "53") (pinfunction "53_53") (pintype "passive"))
    )
    (net (code "41") (name "PCIE_B_CLK_P") (class "Default")
      (node (ref "IC1") (pin "13") (pinfunction "~{DIFF0}_13") (pintype "output"))
      (node (ref "J2") (pin "55") (pinfunction "55_55") (pintype "passive"))
    )
    (net (code "42") (name "PCIE_B_RX0_N") (class "Default")
      (node (ref "J2") (pin "43") (pinfunction "43_43") (pintype "passive"))
      (node (ref "JP1") (pin "A17") (pinfunction "A17_A17") (pintype "bidirectional"))
    )
    (net (code "43") (name "PCIE_B_RX0_P") (class "Default")
      (node (ref "J2") (pin "41") (pinfunction "41_41") (pintype "passive"))
      (node (ref "JP1") (pin "A18") (pinfunction "A18_A18") (pintype "bidirectional"))
    )
    (net (code "44") (name "PCIE_B_RX1_N") (class "Default")
      (node (ref "J2") (pin "31") (pinfunction "31_31") (pintype "passive"))
      (node (ref "JP1") (pin "A20") (pinfunction "A20_A20") (pintype "bidirectional"))
    )
    (net (code "45") (name "PCIE_B_RX1_P") (class "Default")
      (node (ref "J2") (pin "29") (pinfunction "29_29") (pintype "passive"))
      (node (ref "JP1") (pin "A21") (pinfunction "A21_A21") (pintype "bidirectional"))
    )
    (net (code "46") (name "PCIE_B_RX2_N") (class "Default")
      (node (ref "J2") (pin "19") (pinfunction "19_19") (pintype "passive"))
      (node (ref "JP1") (pin "A23") (pinfunction "A23_A23") (pintype "bidirectional"))
    )
    (net (code "47") (name "PCIE_B_RX2_P") (class "Default")
      (node (ref "J2") (pin "17") (pinfunction "17_17") (pintype "passive"))
      (node (ref "JP1") (pin "A24") (pinfunction "A24_A24") (pintype "bidirectional"))
    )
    (net (code "48") (name "PCIE_B_RX3_N") (class "Default")
      (node (ref "J2") (pin "5") (pinfunction "5_5") (pintype "passive"))
      (node (ref "JP1") (pin "A27") (pinfunction "A27_A27") (pintype "bidirectional"))
    )
    (net (code "49") (name "PCIE_B_RX3_P") (class "Default")
      (node (ref "J2") (pin "7") (pinfunction "7_7") (pintype "passive"))
      (node (ref "JP1") (pin "A26") (pinfunction "A26_A26") (pintype "bidirectional"))
    )
    (net (code "50") (name "PCIE_B_TX0_N") (class "Default")
      (node (ref "J2") (pin "49") (pinfunction "49_49") (pintype "passive"))
      (node (ref "JP1") (pin "B16") (pinfunction "B16_B16") (pintype "bidirectional"))
    )
    (net (code "51") (name "PCIE_B_TX0_P") (class "Default")
      (node (ref "J2") (pin "47") (pinfunction "47_47") (pintype "passive"))
      (node (ref "JP1") (pin "B17") (pinfunction "B17_B17") (pintype "bidirectional"))
    )
    (net (code "52") (name "PCIE_B_TX1_N") (class "Default")
      (node (ref "J2") (pin "37") (pinfunction "37_37") (pintype "passive"))
      (node (ref "JP1") (pin "B19") (pinfunction "B19_B19") (pintype "bidirectional"))
    )
    (net (code "53") (name "PCIE_B_TX1_P") (class "Default")
      (node (ref "J2") (pin "35") (pinfunction "35_35") (pintype "passive"))
      (node (ref "JP1") (pin "B20") (pinfunction "B20_B20") (pintype "bidirectional"))
    )
    (net (code "54") (name "PCIE_B_TX2_N") (class "Default")
      (node (ref "J2") (pin "25") (pinfunction "25_25") (pintype "passive"))
      (node (ref "JP1") (pin "B22") (pinfunction "B22_B22") (pintype "bidirectional"))
    )
    (net (code "55") (name "PCIE_B_TX2_P") (class "Default")
      (node (ref "J2") (pin "23") (pinfunction "23_23") (pintype "passive"))
      (node (ref "JP1") (pin "B23") (pinfunction "B23_B23") (pintype "bidirectional"))
    )
    (net (code "56") (name "PCIE_B_TX3_N") (class "Default")
      (node (ref "J2") (pin "11") (pinfunction "11_11") (pintype "passive"))
      (node (ref "JP1") (pin "B25") (pinfunction "B25_B25") (pintype "bidirectional"))
    )
    (net (code "57") (name "PCIE_B_TX3_P") (class "Default")
      (node (ref "J2") (pin "13") (pinfunction "13_13") (pintype "passive"))
      (node (ref "JP1") (pin "B26") (pinfunction "B26_B26") (pintype "bidirectional"))
    )
    (net (code "58") (name "PCIE_C_CLKREQ") (class "Default")
      (node (ref "J1") (pin "52") (pinfunction "52_52") (pintype "passive"))
      (node (ref "JP1") (pin "B14") (pinfunction "B14_B14") (pintype "bidirectional"))
    )
    (net (code "59") (name "PCIE_C_CLK_N") (class "Default")
      (node (ref "J1") (pin "53") (pinfunction "53_53") (pintype "passive"))
      (node (ref "JP1") (pin "A14") (pinfunction "A14_A14") (pintype "bidirectional"))
    )
    (net (code "60") (name "PCIE_C_CLK_P") (class "Default")
      (node (ref "J1") (pin "55") (pinfunction "55_55") (pintype "passive"))
      (node (ref "JP1") (pin "A15") (pinfunction "A15_A15") (pintype "bidirectional"))
    )
    (net (code "61") (name "PCIE_C_RX0_N") (class "Default")
      (node (ref "J1") (pin "41") (pinfunction "41_41") (pintype "passive"))
      (node (ref "JP1") (pin "B11") (pinfunction "B11_B11") (pintype "bidirectional"))
    )
    (net (code "62") (name "PCIE_C_RX0_P") (class "Default")
      (node (ref "J1") (pin "43") (pinfunction "43_43") (pintype "passive"))
      (node (ref "JP1") (pin "B12") (pinfunction "B12_B12") (pintype "bidirectional"))
    )
    (net (code "63") (name "PCIE_C_RX1_N") (class "Default")
      (node (ref "J1") (pin "31") (pinfunction "31_31") (pintype "passive"))
      (node (ref "JP1") (pin "A11") (pinfunction "A11_A11") (pintype "bidirectional"))
    )
    (net (code "64") (name "PCIE_C_RX1_P") (class "Default")
      (node (ref "J1") (pin "29") (pinfunction "29_29") (pintype "passive"))
      (node (ref "JP1") (pin "A12") (pinfunction "A12_A12") (pintype "bidirectional"))
    )
    (net (code "65") (name "PCIE_C_RX2_N") (class "Default")
      (node (ref "J1") (pin "17") (pinfunction "17_17") (pintype "passive"))
      (node (ref "JP1") (pin "A9") (pinfunction "A9_A9") (pintype "bidirectional"))
    )
    (net (code "66") (name "PCIE_C_RX2_P") (class "Default")
      (node (ref "J1") (pin "19") (pinfunction "19_19") (pintype "passive"))
      (node (ref "JP1") (pin "A8") (pinfunction "A8_A8") (pintype "bidirectional"))
    )
    (net (code "67") (name "PCIE_C_RX3_N") (class "Default")
      (node (ref "J1") (pin "7") (pinfunction "7_7") (pintype "passive"))
      (node (ref "JP1") (pin "B8") (pinfunction "B8_B8") (pintype "bidirectional"))
    )
    (net (code "68") (name "PCIE_C_RX3_P") (class "Default")
      (node (ref "J1") (pin "5") (pinfunction "5_5") (pintype "passive"))
      (node (ref "JP1") (pin "B9") (pinfunction "B9_B9") (pintype "bidirectional"))
    )
    (net (code "69") (name "PCIE_C_TX0_N") (class "Default")
      (node (ref "J1") (pin "49") (pinfunction "49_49") (pintype "passive"))
      (node (ref "JP1") (pin "B5") (pinfunction "B5_B5") (pintype "bidirectional"))
    )
    (net (code "70") (name "PCIE_C_TX0_P") (class "Default")
      (node (ref "J1") (pin "47") (pinfunction "47_47") (pintype "passive"))
      (node (ref "JP1") (pin "B6") (pinfunction "B6_B6") (pintype "bidirectional"))
    )
    (net (code "71") (name "PCIE_C_TX1_N") (class "Default")
      (node (ref "J1") (pin "37") (pinfunction "37_37") (pintype "passive"))
      (node (ref "JP1") (pin "A5") (pinfunction "A5_A5") (pintype "bidirectional"))
    )
    (net (code "72") (name "PCIE_C_TX1_P") (class "Default")
      (node (ref "J1") (pin "35") (pinfunction "35_35") (pintype "passive"))
      (node (ref "JP1") (pin "A6") (pinfunction "A6_A6") (pintype "bidirectional"))
    )
    (net (code "73") (name "PCIE_C_TX2_N") (class "Default")
      (node (ref "J1") (pin "25") (pinfunction "25_25") (pintype "passive"))
      (node (ref "JP1") (pin "B2") (pinfunction "B2_B2") (pintype "bidirectional"))
    )
    (net (code "74") (name "PCIE_C_TX2_P") (class "Default")
      (node (ref "J1") (pin "23") (pinfunction "23_23") (pintype "passive"))
      (node (ref "JP1") (pin "B3") (pinfunction "B3_B3") (pintype "bidirectional"))
    )
    (net (code "75") (name "PCIE_C_TX3_N") (class "Default")
      (node (ref "J1") (pin "13") (pinfunction "13_13") (pintype "passive"))
      (node (ref "JP1") (pin "A2") (pinfunction "A2_A2") (pintype "bidirectional"))
    )
    (net (code "76") (name "PCIE_C_TX3_P") (class "Default")
      (node (ref "J1") (pin "11") (pinfunction "11_11") (pintype "passive"))
      (node (ref "JP1") (pin "A3") (pinfunction "A3_A3") (pintype "bidirectional"))
    )
    (net (code "77") (name "SMBCLK") (class "Default")
      (node (ref "IC1") (pin "19") (pinfunction "SCLK_19") (pintype "input"))
      (node (ref "IC2") (pin "8") (pinfunction "GPI/SCL_8") (pintype "input"))
      (node (ref "JP1") (pin "B53") (pinfunction "B53_B53") (pintype "bidirectional"))
      (node (ref "TC1") (pin "6") (pinfunction "P6_6") (pintype "passive"))
    )
    (net (code "78") (name "SMBDAT") (class "Default")
      (node (ref "IC1") (pin "20") (pinfunction "SDATA_20") (pintype "bidirectional"))
      (node (ref "IC2") (pin "9") (pinfunction "GPI/SDA_9") (pintype "input"))
      (node (ref "JP1") (pin "B52") (pinfunction "B52_B52") (pintype "bidirectional"))
      (node (ref "TC1") (pin "4") (pinfunction "P4_4") (pintype "passive"))
    )
    (net (code "79") (name "VCC") (class "Default")
      (node (ref "C1") (pin "1") (pinfunction "1_1") (pintype "passive"))
      (node (ref "C10") (pin "1") (pinfunction "1_1") (pintype "passive"))
      (node (ref "C11") (pin "1") (pinfunction "1_1") (pintype "passive"))
      (node (ref "C2") (pin "1") (pinfunction "1_1") (pintype "passive"))
      (node (ref "C3") (pin "1") (pinfunction "1_1") (pintype "passive"))
      (node (ref "C4") (pin "1") (pinfunction "1_1") (pintype "passive"))
      (node (ref "J1") (pin "12") (pinfunction "12_12") (pintype "passive"))
      (node (ref "J1") (pin "14") (pinfunction "14_14") (pintype "passive"))
      (node (ref "J1") (pin "16") (pinfunction "16_16") (pintype "passive"))
      (node (ref "J1") (pin "18") (pinfunction "18_18") (pintype "passive"))
      (node (ref "J1") (pin "2") (pinfunction "2_2") (pintype "passive"))
      (node (ref "J1") (pin "4") (pinfunction "4_4") (pintype "passive"))
      (node (ref "J1") (pin "70") (pinfunction "70_70") (pintype "passive"))
      (node (ref "J1") (pin "72") (pinfunction "72_72") (pintype "passive"))
      (node (ref "J1") (pin "74") (pinfunction "74_74") (pintype "passive"))
      (node (ref "J2") (pin "12") (pinfunction "12_12") (pintype "passive"))
      (node (ref "J2") (pin "14") (pinfunction "14_14") (pintype "passive"))
      (node (ref "J2") (pin "16") (pinfunction "16_16") (pintype "passive"))
      (node (ref "J2") (pin "18") (pinfunction "18_18") (pintype "passive"))
      (node (ref "J2") (pin "2") (pinfunction "2_2") (pintype "passive"))
      (node (ref "J2") (pin "4") (pinfunction "4_4") (pintype "passive"))
      (node (ref "J2") (pin "70") (pinfunction "70_70") (pintype "passive"))
      (node (ref "J2") (pin "72") (pinfunction "72_72") (pintype "passive"))
      (node (ref "J2") (pin "74") (pinfunction "74_74") (pintype "passive"))
      (node (ref "R5") (pin "2") (pinfunction "2_2") (pintype "passive"))
      (node (ref "U1") (pin "1") (pinfunction "VOUT_1") (pintype "bidirectional"))
      (node (ref "U1") (pin "8") (pinfunction "VOUT_8") (pintype "bidirectional"))
    )
    (net (code "80") (name "VCCINT") (class "Default")
      (node (ref "C13") (pin "1") (pinfunction "1_1") (pintype "passive"))
      (node (ref "IC2") (pin "1") (pinfunction "VDD_1") (pintype "power_in"))
      (node (ref "IC2") (pin "14") (pinfunction "VDD2_14") (pintype "power_in"))
      (node (ref "J3") (pin "B10") (pinfunction "B10_B10") (pintype "passive"))
      (node (ref "JP1") (pin "A50") (pinfunction "A50_A50") (pintype "bidirectional"))
      (node (ref "JP1") (pin "B47") (pinfunction "B47_B47") (pintype "bidirectional"))
      (node (ref "TC1") (pin "2") (pinfunction "P2_2") (pintype "passive"))
    )
    (net (code "81") (name "unconnected-(IC1-NC-Pad11)") (class "Default")
      (node (ref "IC1") (pin "11") (pinfunction "NC_11") (pintype "no_connect"))
    )
    (net (code "82") (name "unconnected-(IC1-NC_2-Pad2)") (class "Default")
      (node (ref "IC1") (pin "2") (pinfunction "NC_2_2") (pintype "no_connect"))
    )
    (net (code "83") (name "unconnected-(IC1-NC_3-Pad7)") (class "Default")
      (node (ref "IC1") (pin "7") (pinfunction "NC_3_7") (pintype "no_connect"))
    )
    (net (code "84") (name "unconnected-(IC1-NC_4-Pad8)") (class "Default")
      (node (ref "IC1") (pin "8") (pinfunction "NC_4_8") (pintype "no_connect"))
    )
    (net (code "85") (name "unconnected-(IC1-NC_5-Pad9)") (class "Default")
      (node (ref "IC1") (pin "9") (pinfunction "NC_5_9") (pintype "no_connect"))
    )
    (net (code "86") (name "unconnected-(IC1-NC_6-Pad10)") (class "Default")
      (node (ref "IC1") (pin "10") (pinfunction "NC_6_10") (pintype "no_connect"))
    )
    (net (code "87") (name "unconnected-(IC2-I{slash}O-Pad3)") (class "Default")
      (node (ref "IC2") (pin "3") (pinfunction "I/O_3") (pintype "bidirectional"))
    )
    (net (code "88") (name "unconnected-(IC2-I{slash}O-Pad4)") (class "Default")
      (node (ref "IC2") (pin "4") (pinfunction "I/O_4") (pintype "bidirectional"))
    )
    (net (code "89") (name "unconnected-(IC2-I{slash}O-Pad5)") (class "Default")
      (node (ref "IC2") (pin "5") (pinfunction "I/O_5") (pintype "bidirectional"))
    )
    (net (code "90") (name "unconnected-(J1-Pad6)") (class "Default")
      (node (ref "J1") (pin "6") (pinfunction "6_6") (pintype "passive"))
    )
    (net (code "91") (name "unconnected-(J1-Pad8)") (class "Default")
      (node (ref "J1") (pin "8") (pinfunction "8_8") (pintype "passive"))
    )
    (net (code "92") (name "unconnected-(J1-Pad10)") (class "Default")
      (node (ref "J1") (pin "10") (pinfunction "10_10") (pintype "passive"))
    )
    (net (code "93") (name "unconnected-(J1-Pad20)") (class "Default")
      (node (ref "J1") (pin "20") (pinfunction "20_20") (pintype "passive"))
    )
    (net (code "94") (name "unconnected-(J1-Pad22)") (class "Default")
      (node (ref "J1") (pin "22") (pinfunction "22_22") (pintype "passive"))
    )
    (net (code "95") (name "unconnected-(J1-Pad24)") (class "Default")
      (node (ref "J1") (pin "24") (pinfunction "24_24") (pintype "passive"))
    )
    (net (code "96") (name "unconnected-(J1-Pad26)") (class "Default")
      (node (ref "J1") (pin "26") (pinfunction "26_26") (pintype "passive"))
    )
    (net (code "97") (name "unconnected-(J1-Pad28)") (class "Default")
      (node (ref "J1") (pin "28") (pinfunction "28_28") (pintype "passive"))
    )
    (net (code "98") (name "unconnected-(J1-Pad30)") (class "Default")
      (node (ref "J1") (pin "30") (pinfunction "30_30") (pintype "passive"))
    )
    (net (code "99") (name "unconnected-(J1-Pad32)") (class "Default")
      (node (ref "J1") (pin "32") (pinfunction "32_32") (pintype "passive"))
    )
    (net (code "100") (name "unconnected-(J1-Pad34)") (class "Default")
      (node (ref "J1") (pin "34") (pinfunction "34_34") (pintype "passive"))
    )
    (net (code "101") (name "unconnected-(J1-Pad36)") (class "Default")
      (node (ref "J1") (pin "36") (pinfunction "36_36") (pintype "passive"))
    )
    (net (code "102") (name "unconnected-(J1-Pad38)") (class "Default")
      (node (ref "J1") (pin "38") (pinfunction "38_38") (pintype "passive"))
    )
    (net (code "103") (name "unconnected-(J1-Pad40)") (class "Default")
      (node (ref "J1") (pin "40") (pinfunction "40_40") (pintype "passive"))
    )
    (net (code "104") (name "unconnected-(J1-Pad42)") (class "Default")
      (node (ref "J1") (pin "42") (pinfunction "42_42") (pintype "passive"))
    )
    (net (code "105") (name "unconnected-(J1-Pad44)") (class "Default")
      (node (ref "J1") (pin "44") (pinfunction "44_44") (pintype "passive"))
    )
    (net (code "106") (name "unconnected-(J1-Pad46)") (class "Default")
      (node (ref "J1") (pin "46") (pinfunction "46_46") (pintype "passive"))
    )
    (net (code "107") (name "unconnected-(J1-Pad48)") (class "Default")
      (node (ref "J1") (pin "48") (pinfunction "48_48") (pintype "passive"))
    )
    (net (code "108") (name "unconnected-(J1-Pad56)") (class "Default")
      (node (ref "J1") (pin "56") (pinfunction "56_56") (pintype "passive"))
    )
    (net (code "109") (name "unconnected-(J1-Pad58)") (class "Default")
      (node (ref "J1") (pin "58") (pinfunction "58_58") (pintype "passive"))
    )
    (net (code "110") (name "unconnected-(J1-Pad67)") (class "Default")
      (node (ref "J1") (pin "67") (pinfunction "67_67") (pintype "passive"))
    )
    (net (code "111") (name "unconnected-(J1-Pad69)") (class "Default")
      (node (ref "J1") (pin "69") (pinfunction "69_69") (pintype "passive"))
    )
    (net (code "112") (name "unconnected-(J2-Pad6)") (class "Default")
      (node (ref "J2") (pin "6") (pinfunction "6_6") (pintype "passive"))
    )
    (net (code "113") (name "unconnected-(J2-Pad8)") (class "Default")
      (node (ref "J2") (pin "8") (pinfunction "8_8") (pintype "passive"))
    )
    (net (code "114") (name "unconnected-(J2-Pad10)") (class "Default")
      (node (ref "J2") (pin "10") (pinfunction "10_10") (pintype "passive"))
    )
    (net (code "115") (name "unconnected-(J2-Pad20)") (class "Default")
      (node (ref "J2") (pin "20") (pinfunction "20_20") (pintype "passive"))
    )
    (net (code "116") (name "unconnected-(J2-Pad22)") (class "Default")
      (node (ref "J2") (pin "22") (pinfunction "22_22") (pintype "passive"))
    )
    (net (code "117") (name "unconnected-(J2-Pad24)") (class "Default")
      (node (ref "J2") (pin "24") (pinfunction "24_24") (pintype "passive"))
    )
    (net (code "118") (name "unconnected-(J2-Pad26)") (class "Default")
      (node (ref "J2") (pin "26") (pinfunction "26_26") (pintype "passive"))
    )
    (net (code "119") (name "unconnected-(J2-Pad28)") (class "Default")
      (node (ref "J2") (pin "28") (pinfunction "28_28") (pintype "passive"))
    )
    (net (code "120") (name "unconnected-(J2-Pad30)") (class "Default")
      (node (ref "J2") (pin "30") (pinfunction "30_30") (pintype "passive"))
    )
    (net (code "121") (name "unconnected-(J2-Pad32)") (class "Default")
      (node (ref "J2") (pin "32") (pinfunction "32_32") (pintype "passive"))
    )
    (net (code "122") (name "unconnected-(J2-Pad34)") (class "Default")
      (node (ref "J2") (pin "34") (pinfunction "34_34") (pintype "passive"))
    )
    (net (code "123") (name "unconnected-(J2-Pad36)") (class "Default")
      (node (ref "J2") (pin "36") (pinfunction "36_36") (pintype "passive"))
    )
    (net (code "124") (name "unconnected-(J2-Pad38)") (class "Default")
      (node (ref "J2") (pin "38") (pinfunction "38_38") (pintype "passive"))
    )
    (net (code "125") (name "unconnected-(J2-Pad40)") (class "Default")
      (node (ref "J2") (pin "40") (pinfunction "40_40") (pintype "passive"))
    )
    (net (code "126") (name "unconnected-(J2-Pad42)") (class "Default")
      (node (ref "J2") (pin "42") (pinfunction "42_42") (pintype "passive"))
    )
    (net (code "127") (name "unconnected-(J2-Pad44)") (class "Default")
      (node (ref "J2") (pin "44") (pinfunction "44_44") (pintype "passive"))
    )
    (net (code "128") (name "unconnected-(J2-Pad46)") (class "Default")
      (node (ref "J2") (pin "46") (pinfunction "46_46") (pintype "passive"))
    )
    (net (code "129") (name "unconnected-(J2-Pad48)") (class "Default")
      (node (ref "J2") (pin "48") (pinfunction "48_48") (pintype "passive"))
    )
    (net (code "130") (name "unconnected-(J2-Pad56)") (class "Default")
      (node (ref "J2") (pin "56") (pinfunction "56_56") (pintype "passive"))
    )
    (net (code "131") (name "unconnected-(J2-Pad58)") (class "Default")
      (node (ref "J2") (pin "58") (pinfunction "58_58") (pintype "passive"))
    )
    (net (code "132") (name "unconnected-(J2-Pad67)") (class "Default")
      (node (ref "J2") (pin "67") (pinfunction "67_67") (pintype "passive"))
    )
    (net (code "133") (name "unconnected-(J2-Pad69)") (class "Default")
      (node (ref "J2") (pin "69") (pinfunction "69_69") (pintype "passive"))
    )
    (net (code "134") (name "unconnected-(J3-PadA5)") (class "Default")
      (node (ref "J3") (pin "A5") (pinfunction "A5_A5") (pintype "passive"))
    )
    (net (code "135") (name "unconnected-(J3-PadA6)") (class "Default")
      (node (ref "J3") (pin "A6") (pinfunction "A6_A6") (pintype "passive"))
    )
    (net (code "136") (name "unconnected-(J3-PadA7)") (class "Default")
      (node (ref "J3") (pin "A7") (pinfunction "A7_A7") (pintype "passive"))
    )
    (net (code "137") (name "unconnected-(J3-PadA8)") (class "Default")
      (node (ref "J3") (pin "A8") (pinfunction "A8_A8") (pintype "passive"))
    )
    (net (code "138") (name "unconnected-(J3-PadA19)") (class "Default")
      (node (ref "J3") (pin "A19") (pinfunction "A19_A19") (pintype "passive"))
    )
    (net (code "139") (name "unconnected-(J3-PadA32)") (class "Default")
      (node (ref "J3") (pin "A32") (pinfunction "A32_A32") (pintype "passive"))
    )
    (net (code "140") (name "unconnected-(J3-PadB5)") (class "Default")
      (node (ref "J3") (pin "B5") (pinfunction "B5_B5") (pintype "passive"))
    )
    (net (code "141") (name "unconnected-(J3-PadB6)") (class "Default")
      (node (ref "J3") (pin "B6") (pinfunction "B6_B6") (pintype "passive"))
    )
    (net (code "142") (name "unconnected-(J3-PadB9)") (class "Default")
      (node (ref "J3") (pin "B9") (pinfunction "B9_B9") (pintype "passive"))
    )
    (net (code "143") (name "unconnected-(J3-PadB12)") (class "Default")
      (node (ref "J3") (pin "B12") (pinfunction "B12_B12") (pintype "passive"))
    )
    (net (code "144") (name "unconnected-(J3-PadB30)") (class "Default")
      (node (ref "J3") (pin "B30") (pinfunction "B30_B30") (pintype "passive"))
    )
    (net (code "145") (name "unconnected-(J4-Pad3)") (class "Default")
      (node (ref "J4") (pin "3") (pinfunction "3_3") (pintype "passive"))
    )
    (net (code "146") (name "unconnected-(JP1-PadA1)") (class "Default")
      (node (ref "JP1") (pin "A1") (pinfunction "A1_A1") (pintype "bidirectional"))
    )
    (net (code "147") (name "unconnected-(JP1-PadA60)") (class "Default")
      (node (ref "JP1") (pin "A60") (pinfunction "A60_A60") (pintype "bidirectional"))
    )
    (net (code "148") (name "unconnected-(JP1-PadB1)") (class "Default")
      (node (ref "JP1") (pin "B1") (pinfunction "B1_B1") (pintype "bidirectional"))
    )
    (net (code "149") (name "unconnected-(JP1-PadB28)") (class "Default")
      (node (ref "JP1") (pin "B28") (pinfunction "B28_B28") (pintype "bidirectional"))
    )
  )
)
